# LedTile200mm.net
KiCad netlist of a schematic drawn in EAGLE
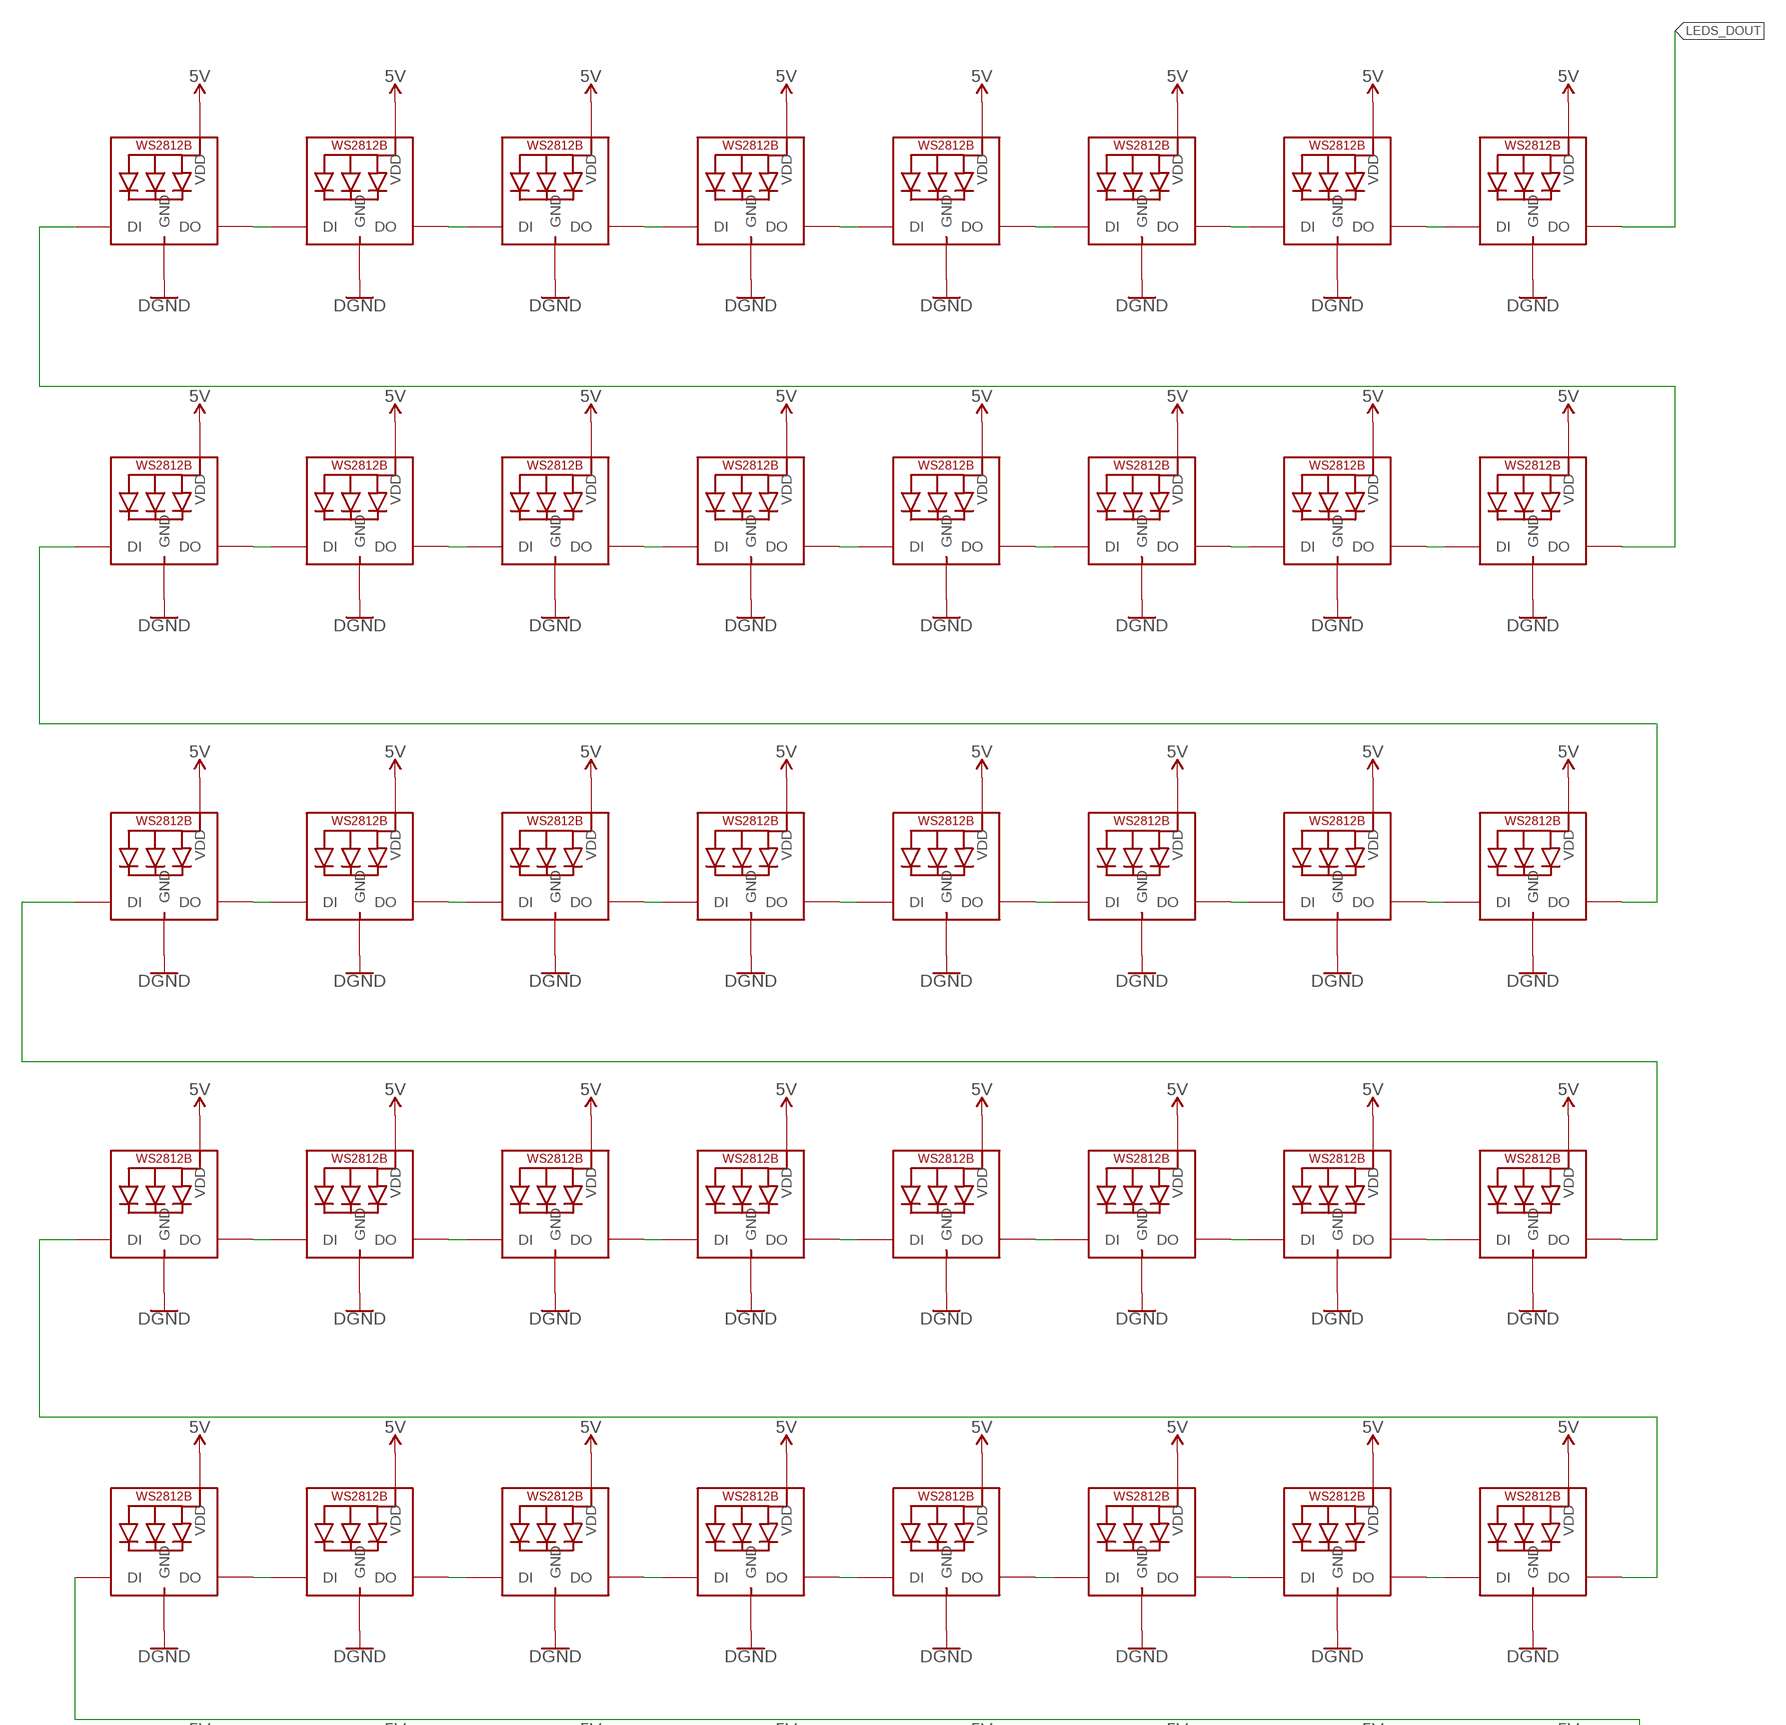
[diagram p0: schematic, sheet 1, part 1 of 3]
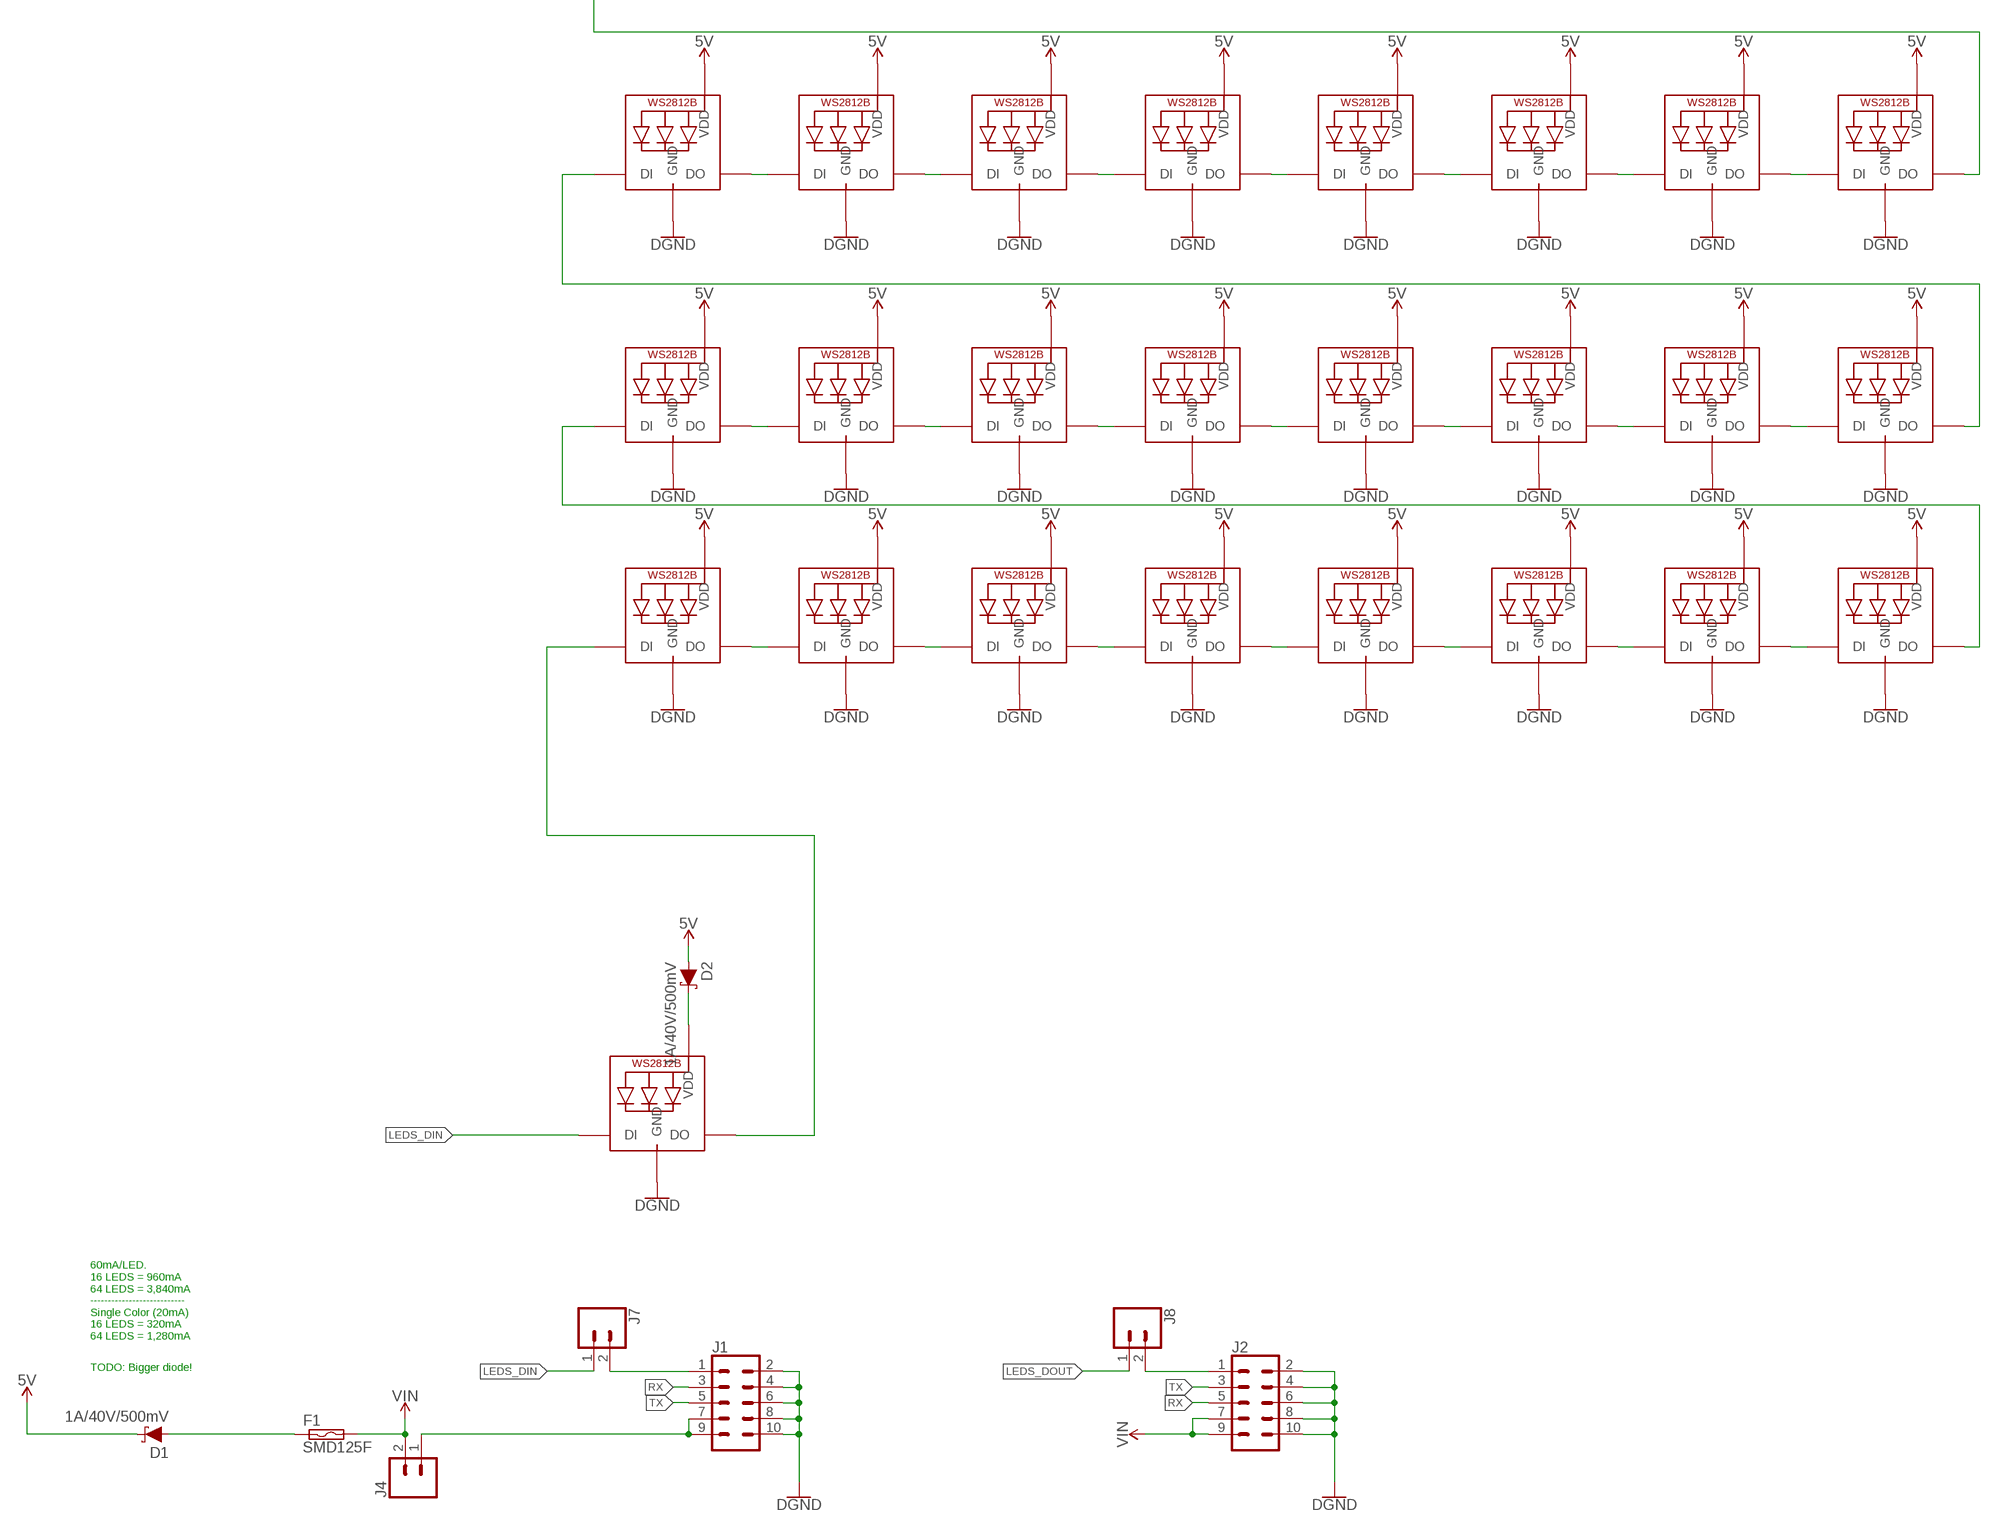
[diagram p1: schematic, sheet 1, part 2 of 3]
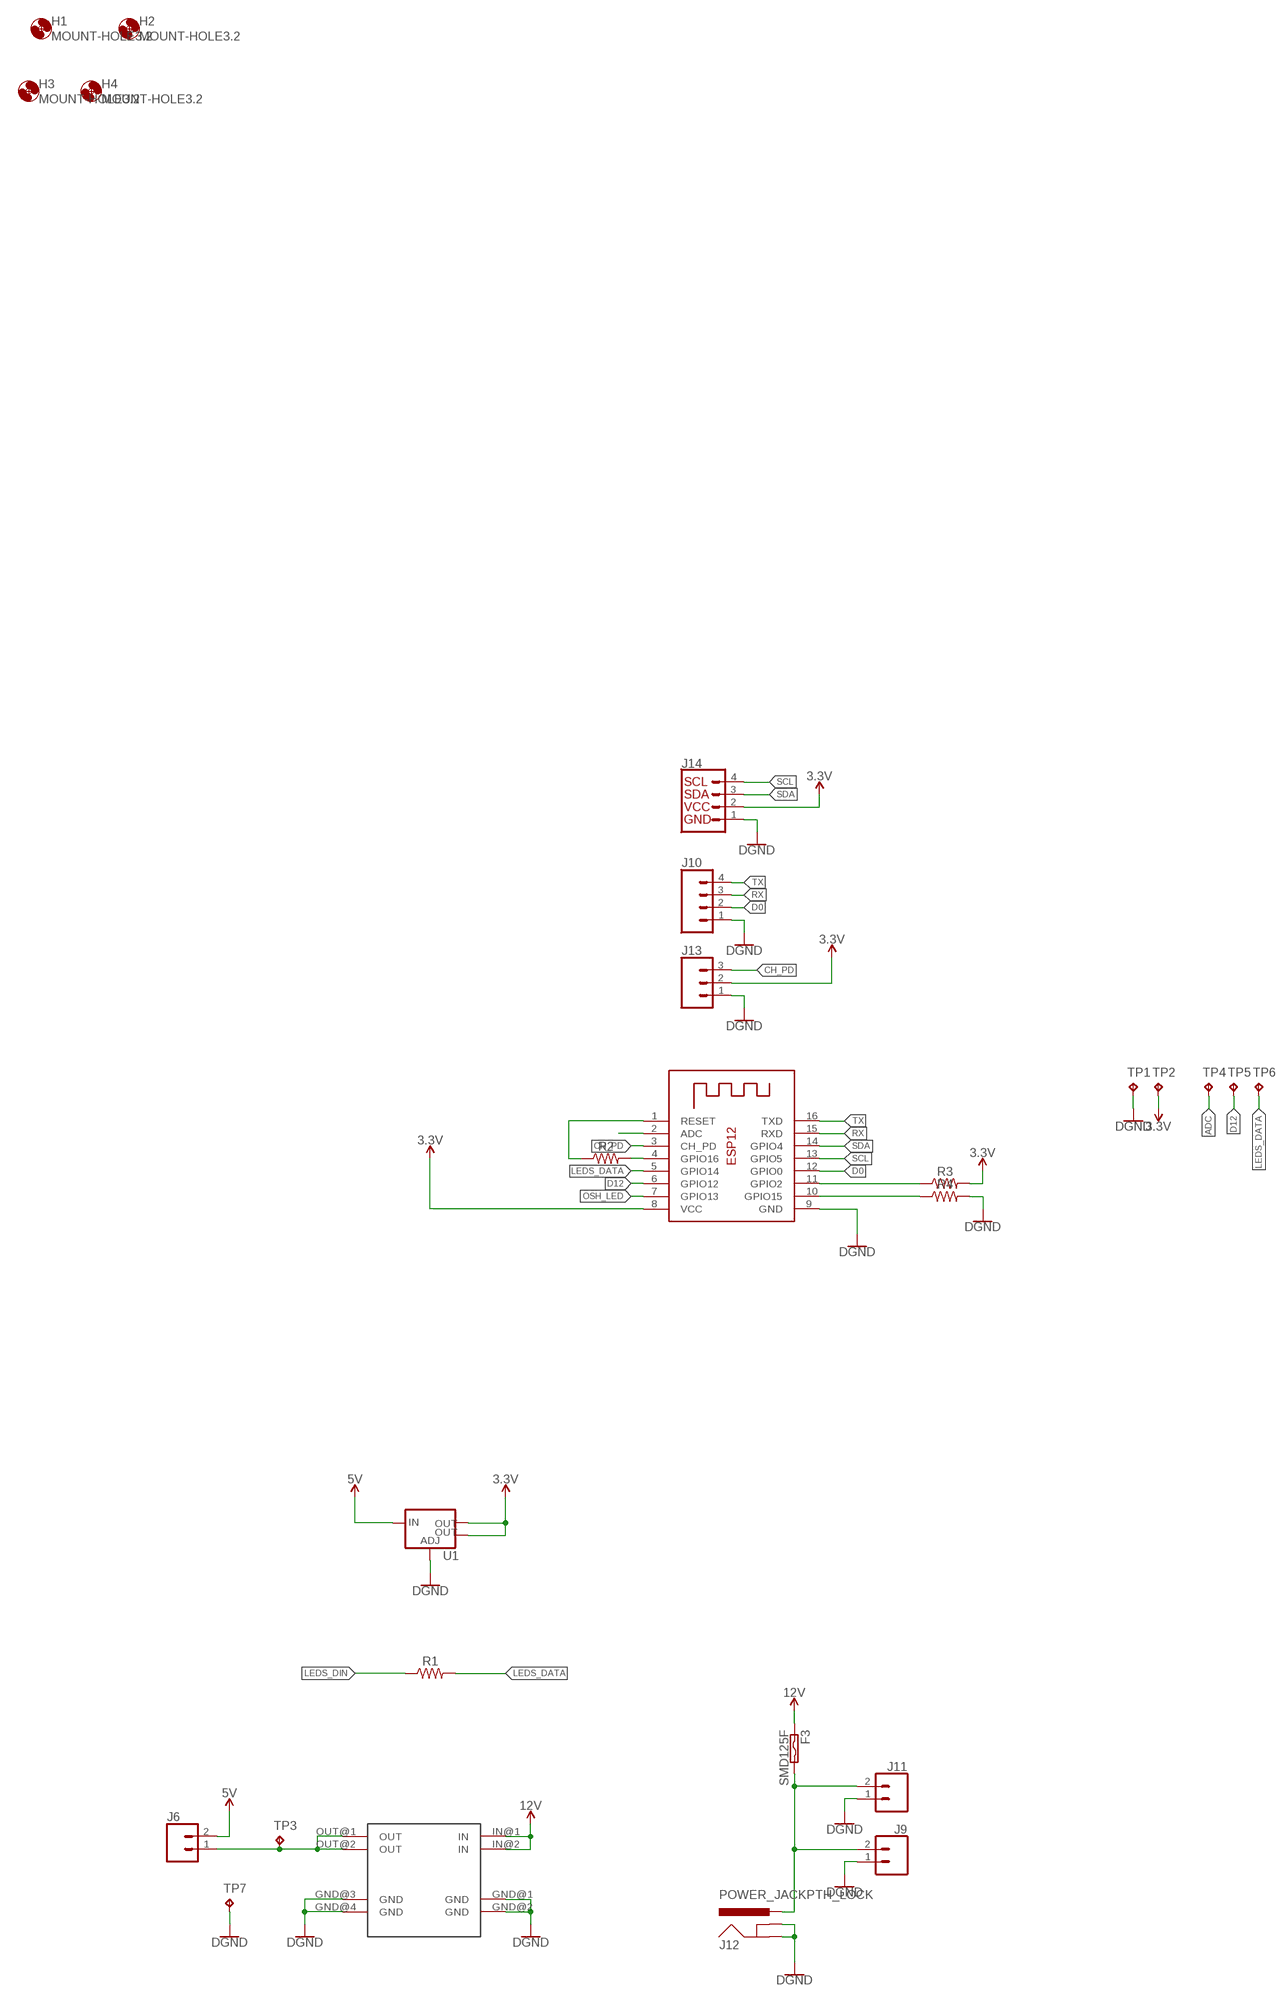
[diagram p2: schematic, sheet 1, part 3 of 3]

(export (version "E")
  (design (tool "Eeschema 10.0.6"))
  (components
    (comp (ref "D1")
      (value "1A/40V/500mV")
      (footprint "eagle-import:SMA-DIODE")
      (libsource (lib "eagle-import") (part "DIODE-SCHOTTKY-SS14"))
    )
    (comp (ref "D2")
      (value "1A/40V/500mV")
      (footprint "eagle-import:SMA-DIODE")
      (libsource (lib "eagle-import") (part "DIODE-SCHOTTKY-SS14"))
    )
    (comp (ref "F1")
      (value "SMD125F")
      (footprint "eagle-import:SMD050F")
      (libsource (lib "eagle-import") (part "SMDF125"))
    )
    (comp (ref "F3")
      (value "SMD125F")
      (footprint "eagle-import:SMD050F")
      (libsource (lib "eagle-import") (part "SMDF125"))
    )
    (comp (ref "H1")
      (value "MOUNT-HOLE3.2")
      (footprint "eagle-import:3,2")
      (libsource (lib "eagle-import") (part "MOUNT-HOLE3.2"))
    )
    (comp (ref "H2")
      (value "MOUNT-HOLE3.2")
      (footprint "eagle-import:3,2")
      (libsource (lib "eagle-import") (part "MOUNT-HOLE3.2"))
    )
    (comp (ref "H3")
      (value "MOUNT-HOLE3.2")
      (footprint "eagle-import:3,2")
      (libsource (lib "eagle-import") (part "MOUNT-HOLE3.2"))
    )
    (comp (ref "H4")
      (value "MOUNT-HOLE3.2")
      (footprint "eagle-import:3,2")
      (libsource (lib "eagle-import") (part "MOUNT-HOLE3.2"))
    )
    (comp (ref "J1")
      (value "CONN_05X2RA")
      (footprint "eagle-import:2X5-RA")
      (libsource (lib "eagle-import") (part "CONN_05X2RA"))
    )
    (comp (ref "J2")
      (value "CONN_05X2RA")
      (footprint "eagle-import:2X5-RA")
      (libsource (lib "eagle-import") (part "CONN_05X2RA"))
    )
    (comp (ref "J4")
      (value "CONN_02")
      (footprint "eagle-import:1X02")
      (libsource (lib "eagle-import") (part "CONN_02"))
    )
    (comp (ref "J6")
      (value "CONN_02")
      (footprint "eagle-import:1X02")
      (libsource (lib "eagle-import") (part "CONN_02"))
    )
    (comp (ref "J7")
      (value "CONN_02")
      (footprint "eagle-import:1X02")
      (libsource (lib "eagle-import") (part "CONN_02"))
    )
    (comp (ref "J8")
      (value "CONN_02")
      (footprint "eagle-import:1X02")
      (libsource (lib "eagle-import") (part "CONN_02"))
    )
    (comp (ref "J9")
      (value "CONN_025MM")
      (footprint "eagle-import:SCREWTERMINAL-5MM-2")
      (libsource (lib "eagle-import") (part "CONN_025MM"))
    )
    (comp (ref "J10")
      (value "CONN_04")
      (footprint "eagle-import:1X04")
      (libsource (lib "eagle-import") (part "CONN_04"))
    )
    (comp (ref "J11")
      (value "CONN_025MM")
      (footprint "eagle-import:SCREWTERMINAL-5MM-2")
      (libsource (lib "eagle-import") (part "CONN_025MM"))
    )
    (comp (ref "J12")
      (value "POWER_JACKPTH_LOCK")
      (footprint "eagle-import:POWER_JACK_PTH_LOCK")
      (libsource (lib "eagle-import") (part "POWER_JACKPTH_LOCK"))
    )
    (comp (ref "J13")
      (value "CONN_03")
      (footprint "eagle-import:1X03")
      (libsource (lib "eagle-import") (part "CONN_03"))
    )
    (comp (ref "J14")
      (value "I2C_STANDARD")
      (footprint "eagle-import:1X04")
      (libsource (lib "eagle-import") (part "I2C_STANDARD"))
    )
    (comp (ref "LED1")
      (value "WS2812B5050")
      (footprint "eagle-import:WS2812B")
      (libsource (lib "eagle-import") (part "WS2812B5050"))
    )
    (comp (ref "LED2")
      (value "WS2812B5050")
      (footprint "eagle-import:WS2812B")
      (libsource (lib "eagle-import") (part "WS2812B5050"))
    )
    (comp (ref "LED3")
      (value "WS2812B5050")
      (footprint "eagle-import:WS2812B")
      (libsource (lib "eagle-import") (part "WS2812B5050"))
    )
    (comp (ref "LED4")
      (value "WS2812B5050")
      (footprint "eagle-import:WS2812B")
      (libsource (lib "eagle-import") (part "WS2812B5050"))
    )
    (comp (ref "LED5")
      (value "WS2812B5050")
      (footprint "eagle-import:WS2812B")
      (libsource (lib "eagle-import") (part "WS2812B5050"))
    )
    (comp (ref "LED6")
      (value "WS2812B5050")
      (footprint "eagle-import:WS2812B")
      (libsource (lib "eagle-import") (part "WS2812B5050"))
    )
    (comp (ref "LED7")
      (value "WS2812B5050")
      (footprint "eagle-import:WS2812B")
      (libsource (lib "eagle-import") (part "WS2812B5050"))
    )
    (comp (ref "LED8")
      (value "WS2812B5050")
      (footprint "eagle-import:WS2812B")
      (libsource (lib "eagle-import") (part "WS2812B5050"))
    )
    (comp (ref "LED9")
      (value "WS2812B5050")
      (footprint "eagle-import:WS2812B")
      (libsource (lib "eagle-import") (part "WS2812B5050"))
    )
    (comp (ref "LED10")
      (value "WS2812B5050")
      (footprint "eagle-import:WS2812B")
      (libsource (lib "eagle-import") (part "WS2812B5050"))
    )
    (comp (ref "LED11")
      (value "WS2812B5050")
      (footprint "eagle-import:WS2812B")
      (libsource (lib "eagle-import") (part "WS2812B5050"))
    )
    (comp (ref "LED12")
      (value "WS2812B5050")
      (footprint "eagle-import:WS2812B")
      (libsource (lib "eagle-import") (part "WS2812B5050"))
    )
    (comp (ref "LED13")
      (value "WS2812B5050")
      (footprint "eagle-import:WS2812B")
      (libsource (lib "eagle-import") (part "WS2812B5050"))
    )
    (comp (ref "LED14")
      (value "WS2812B5050")
      (footprint "eagle-import:WS2812B")
      (libsource (lib "eagle-import") (part "WS2812B5050"))
    )
    (comp (ref "LED15")
      (value "WS2812B5050")
      (footprint "eagle-import:WS2812B")
      (libsource (lib "eagle-import") (part "WS2812B5050"))
    )
    (comp (ref "LED16")
      (value "WS2812B5050")
      (footprint "eagle-import:WS2812B")
      (libsource (lib "eagle-import") (part "WS2812B5050"))
    )
    (comp (ref "LED17")
      (value "WS2812B5050")
      (footprint "eagle-import:WS2812B")
      (libsource (lib "eagle-import") (part "WS2812B5050"))
    )
    (comp (ref "LED18")
      (value "WS2812B5050")
      (footprint "eagle-import:WS2812B")
      (libsource (lib "eagle-import") (part "WS2812B5050"))
    )
    (comp (ref "LED19")
      (value "WS2812B5050")
      (footprint "eagle-import:WS2812B")
      (libsource (lib "eagle-import") (part "WS2812B5050"))
    )
    (comp (ref "LED20")
      (value "WS2812B5050")
      (footprint "eagle-import:WS2812B")
      (libsource (lib "eagle-import") (part "WS2812B5050"))
    )
    (comp (ref "LED21")
      (value "WS2812B5050")
      (footprint "eagle-import:WS2812B")
      (libsource (lib "eagle-import") (part "WS2812B5050"))
    )
    (comp (ref "LED22")
      (value "WS2812B5050")
      (footprint "eagle-import:WS2812B")
      (libsource (lib "eagle-import") (part "WS2812B5050"))
    )
    (comp (ref "LED23")
      (value "WS2812B5050")
      (footprint "eagle-import:WS2812B")
      (libsource (lib "eagle-import") (part "WS2812B5050"))
    )
    (comp (ref "LED24")
      (value "WS2812B5050")
      (footprint "eagle-import:WS2812B")
      (libsource (lib "eagle-import") (part "WS2812B5050"))
    )
    (comp (ref "LED25")
      (value "WS2812B5050")
      (footprint "eagle-import:WS2812B")
      (libsource (lib "eagle-import") (part "WS2812B5050"))
    )
    (comp (ref "LED26")
      (value "WS2812B5050")
      (footprint "eagle-import:WS2812B")
      (libsource (lib "eagle-import") (part "WS2812B5050"))
    )
    (comp (ref "LED27")
      (value "WS2812B5050")
      (footprint "eagle-import:WS2812B")
      (libsource (lib "eagle-import") (part "WS2812B5050"))
    )
    (comp (ref "LED28")
      (value "WS2812B5050")
      (footprint "eagle-import:WS2812B")
      (libsource (lib "eagle-import") (part "WS2812B5050"))
    )
    (comp (ref "LED29")
      (value "WS2812B5050")
      (footprint "eagle-import:WS2812B")
      (libsource (lib "eagle-import") (part "WS2812B5050"))
    )
    (comp (ref "LED30")
      (value "WS2812B5050")
      (footprint "eagle-import:WS2812B")
      (libsource (lib "eagle-import") (part "WS2812B5050"))
    )
    (comp (ref "LED31")
      (value "WS2812B5050")
      (footprint "eagle-import:WS2812B")
      (libsource (lib "eagle-import") (part "WS2812B5050"))
    )
    (comp (ref "LED32")
      (value "WS2812B5050")
      (footprint "eagle-import:WS2812B")
      (libsource (lib "eagle-import") (part "WS2812B5050"))
    )
    (comp (ref "LED33")
      (value "WS2812B5050")
      (footprint "eagle-import:WS2812B")
      (libsource (lib "eagle-import") (part "WS2812B5050"))
    )
    (comp (ref "LED34")
      (value "WS2812B5050")
      (footprint "eagle-import:WS2812B")
      (libsource (lib "eagle-import") (part "WS2812B5050"))
    )
    (comp (ref "LED35")
      (value "WS2812B5050")
      (footprint "eagle-import:WS2812B")
      (libsource (lib "eagle-import") (part "WS2812B5050"))
    )
    (comp (ref "LED36")
      (value "WS2812B5050")
      (footprint "eagle-import:WS2812B")
      (libsource (lib "eagle-import") (part "WS2812B5050"))
    )
    (comp (ref "LED37")
      (value "WS2812B5050")
      (footprint "eagle-import:WS2812B")
      (libsource (lib "eagle-import") (part "WS2812B5050"))
    )
    (comp (ref "LED38")
      (value "WS2812B5050")
      (footprint "eagle-import:WS2812B")
      (libsource (lib "eagle-import") (part "WS2812B5050"))
    )
    (comp (ref "LED39")
      (value "WS2812B5050")
      (footprint "eagle-import:WS2812B")
      (libsource (lib "eagle-import") (part "WS2812B5050"))
    )
    (comp (ref "LED40")
      (value "WS2812B5050")
      (footprint "eagle-import:WS2812B")
      (libsource (lib "eagle-import") (part "WS2812B5050"))
    )
    (comp (ref "LED41")
      (value "WS2812B5050")
      (footprint "eagle-import:WS2812B")
      (libsource (lib "eagle-import") (part "WS2812B5050"))
    )
    (comp (ref "LED42")
      (value "WS2812B5050")
      (footprint "eagle-import:WS2812B")
      (libsource (lib "eagle-import") (part "WS2812B5050"))
    )
    (comp (ref "LED43")
      (value "WS2812B5050")
      (footprint "eagle-import:WS2812B")
      (libsource (lib "eagle-import") (part "WS2812B5050"))
    )
    (comp (ref "LED44")
      (value "WS2812B5050")
      (footprint "eagle-import:WS2812B")
      (libsource (lib "eagle-import") (part "WS2812B5050"))
    )
    (comp (ref "LED45")
      (value "WS2812B5050")
      (footprint "eagle-import:WS2812B")
      (libsource (lib "eagle-import") (part "WS2812B5050"))
    )
    (comp (ref "LED46")
      (value "WS2812B5050")
      (footprint "eagle-import:WS2812B")
      (libsource (lib "eagle-import") (part "WS2812B5050"))
    )
    (comp (ref "LED47")
      (value "WS2812B5050")
      (footprint "eagle-import:WS2812B")
      (libsource (lib "eagle-import") (part "WS2812B5050"))
    )
    (comp (ref "LED48")
      (value "WS2812B5050")
      (footprint "eagle-import:WS2812B")
      (libsource (lib "eagle-import") (part "WS2812B5050"))
    )
    (comp (ref "LED49")
      (value "WS2812B5050")
      (footprint "eagle-import:WS2812B")
      (libsource (lib "eagle-import") (part "WS2812B5050"))
    )
    (comp (ref "LED50")
      (value "WS2812B5050")
      (footprint "eagle-import:WS2812B")
      (libsource (lib "eagle-import") (part "WS2812B5050"))
    )
    (comp (ref "LED51")
      (value "WS2812B5050")
      (footprint "eagle-import:WS2812B")
      (libsource (lib "eagle-import") (part "WS2812B5050"))
    )
    (comp (ref "LED52")
      (value "WS2812B5050")
      (footprint "eagle-import:WS2812B")
      (libsource (lib "eagle-import") (part "WS2812B5050"))
    )
    (comp (ref "LED53")
      (value "WS2812B5050")
      (footprint "eagle-import:WS2812B")
      (libsource (lib "eagle-import") (part "WS2812B5050"))
    )
    (comp (ref "LED54")
      (value "WS2812B5050")
      (footprint "eagle-import:WS2812B")
      (libsource (lib "eagle-import") (part "WS2812B5050"))
    )
    (comp (ref "LED55")
      (value "WS2812B5050")
      (footprint "eagle-import:WS2812B")
      (libsource (lib "eagle-import") (part "WS2812B5050"))
    )
    (comp (ref "LED56")
      (value "WS2812B5050")
      (footprint "eagle-import:WS2812B")
      (libsource (lib "eagle-import") (part "WS2812B5050"))
    )
    (comp (ref "LED57")
      (value "WS2812B5050")
      (footprint "eagle-import:WS2812B")
      (libsource (lib "eagle-import") (part "WS2812B5050"))
    )
    (comp (ref "LED58")
      (value "WS2812B5050")
      (footprint "eagle-import:WS2812B")
      (libsource (lib "eagle-import") (part "WS2812B5050"))
    )
    (comp (ref "LED59")
      (value "WS2812B5050")
      (footprint "eagle-import:WS2812B")
      (libsource (lib "eagle-import") (part "WS2812B5050"))
    )
    (comp (ref "LED60")
      (value "WS2812B5050")
      (footprint "eagle-import:WS2812B")
      (libsource (lib "eagle-import") (part "WS2812B5050"))
    )
    (comp (ref "LED61")
      (value "WS2812B5050")
      (footprint "eagle-import:WS2812B")
      (libsource (lib "eagle-import") (part "WS2812B5050"))
    )
    (comp (ref "LED62")
      (value "WS2812B5050")
      (footprint "eagle-import:WS2812B")
      (libsource (lib "eagle-import") (part "WS2812B5050"))
    )
    (comp (ref "LED63")
      (value "WS2812B5050")
      (footprint "eagle-import:WS2812B")
      (libsource (lib "eagle-import") (part "WS2812B5050"))
    )
    (comp (ref "LED64")
      (value "WS2812B5050")
      (footprint "eagle-import:WS2812B")
      (libsource (lib "eagle-import") (part "WS2812B5050"))
    )
    (comp (ref "LED65")
      (value "WS2812B5050")
      (footprint "eagle-import:WS2812B")
      (libsource (lib "eagle-import") (part "WS2812B5050"))
    )
    (comp (ref "R1")
      (value "RESISTOR0805")
      (footprint "eagle-import:0805")
      (libsource (lib "eagle-import") (part "RESISTOR0805"))
    )
    (comp (ref "R2")
      (value "RESISTOR0805")
      (footprint "eagle-import:0805")
      (libsource (lib "eagle-import") (part "RESISTOR0805"))
    )
    (comp (ref "R3")
      (value "RESISTOR0805")
      (footprint "eagle-import:0805")
      (libsource (lib "eagle-import") (part "RESISTOR0805"))
    )
    (comp (ref "R4")
      (value "RESISTOR0805")
      (footprint "eagle-import:0805")
      (libsource (lib "eagle-import") (part "RESISTOR0805"))
    )
    (comp (ref "TP1")
      (value "TPTP16R")
      (footprint "eagle-import:TP16R")
      (libsource (lib "eagle-import") (part "TPTP16R"))
    )
    (comp (ref "TP2")
      (value "TPTP16R")
      (footprint "eagle-import:TP16R")
      (libsource (lib "eagle-import") (part "TPTP16R"))
    )
    (comp (ref "TP3")
      (value "TPTP16R")
      (footprint "eagle-import:TP16R")
      (libsource (lib "eagle-import") (part "TPTP16R"))
    )
    (comp (ref "TP4")
      (value "TPTP16R")
      (footprint "eagle-import:TP16R")
      (libsource (lib "eagle-import") (part "TPTP16R"))
    )
    (comp (ref "TP5")
      (value "TPTP16R")
      (footprint "eagle-import:TP16R")
      (libsource (lib "eagle-import") (part "TPTP16R"))
    )
    (comp (ref "TP6")
      (value "TPTP16R")
      (footprint "eagle-import:TP16R")
      (libsource (lib "eagle-import") (part "TPTP16R"))
    )
    (comp (ref "TP7")
      (value "TPTP16R")
      (footprint "eagle-import:TP16R")
      (libsource (lib "eagle-import") (part "TPTP16R"))
    )
    (comp (ref "U$1")
      (value "MINI-BUCK-MODULE-3A")
      (footprint "eagle-import:MINI-BUCK-MODULE-3A")
      (libsource (lib "eagle-import") (part "MINI-BUCK-MODULE-3A"))
    )
    (comp (ref "U1")
      (value "V_REG_LM1117SOT223")
      (footprint "eagle-import:SOT223")
      (libsource (lib "eagle-import") (part "V_REG_LM1117SOT223"))
    )
    (comp (ref "X1")
      (value "ESP-12")
      (footprint "eagle-import:ESP-12")
      (libsource (lib "eagle-import") (part "ESP-12"))
    )
  )
  (nets
    (net (code "1") (name "3.3V") (class "Default")
      (node (ref "J13") (pin "2") (pinfunction "2_2") (pintype "passive"))
      (node (ref "J14") (pin "2") (pinfunction "2_2") (pintype "power_in"))
      (node (ref "R3") (pin "2") (pinfunction "2_2") (pintype "passive"))
      (node (ref "TP2") (pin "TP") (pinfunction "TP_TP") (pintype "input"))
      (node (ref "U1") (pin "2") (pinfunction "OUT_2") (pintype "output"))
      (node (ref "U1") (pin "4") (pinfunction "OUT_4") (pintype "output"))
      (node (ref "X1") (pin "8") (pinfunction "VCC_8") (pintype "power_in"))
    )
    (net (code "2") (name "5V") (class "Default")
      (node (ref "D1") (pin "C") (pinfunction "C_C") (pintype "passive"))
      (node (ref "D2") (pin "A") (pinfunction "A_A") (pintype "passive"))
      (node (ref "J6") (pin "2") (pinfunction "2_2") (pintype "passive"))
      (node (ref "LED1") (pin "1-VDD") (pinfunction "VDD_1-VDD") (pintype "power_in"))
      (node (ref "LED10") (pin "1-VDD") (pinfunction "VDD_1-VDD") (pintype "power_in"))
      (node (ref "LED11") (pin "1-VDD") (pinfunction "VDD_1-VDD") (pintype "power_in"))
      (node (ref "LED12") (pin "1-VDD") (pinfunction "VDD_1-VDD") (pintype "power_in"))
      (node (ref "LED13") (pin "1-VDD") (pinfunction "VDD_1-VDD") (pintype "power_in"))
      (node (ref "LED14") (pin "1-VDD") (pinfunction "VDD_1-VDD") (pintype "power_in"))
      (node (ref "LED15") (pin "1-VDD") (pinfunction "VDD_1-VDD") (pintype "power_in"))
      (node (ref "LED16") (pin "1-VDD") (pinfunction "VDD_1-VDD") (pintype "power_in"))
      (node (ref "LED17") (pin "1-VDD") (pinfunction "VDD_1-VDD") (pintype "power_in"))
      (node (ref "LED18") (pin "1-VDD") (pinfunction "VDD_1-VDD") (pintype "power_in"))
      (node (ref "LED19") (pin "1-VDD") (pinfunction "VDD_1-VDD") (pintype "power_in"))
      (node (ref "LED2") (pin "1-VDD") (pinfunction "VDD_1-VDD") (pintype "power_in"))
      (node (ref "LED20") (pin "1-VDD") (pinfunction "VDD_1-VDD") (pintype "power_in"))
      (node (ref "LED21") (pin "1-VDD") (pinfunction "VDD_1-VDD") (pintype "power_in"))
      (node (ref "LED22") (pin "1-VDD") (pinfunction "VDD_1-VDD") (pintype "power_in"))
      (node (ref "LED23") (pin "1-VDD") (pinfunction "VDD_1-VDD") (pintype "power_in"))
      (node (ref "LED24") (pin "1-VDD") (pinfunction "VDD_1-VDD") (pintype "power_in"))
      (node (ref "LED25") (pin "1-VDD") (pinfunction "VDD_1-VDD") (pintype "power_in"))
      (node (ref "LED26") (pin "1-VDD") (pinfunction "VDD_1-VDD") (pintype "power_in"))
      (node (ref "LED27") (pin "1-VDD") (pinfunction "VDD_1-VDD") (pintype "power_in"))
      (node (ref "LED28") (pin "1-VDD") (pinfunction "VDD_1-VDD") (pintype "power_in"))
      (node (ref "LED29") (pin "1-VDD") (pinfunction "VDD_1-VDD") (pintype "power_in"))
      (node (ref "LED3") (pin "1-VDD") (pinfunction "VDD_1-VDD") (pintype "power_in"))
      (node (ref "LED30") (pin "1-VDD") (pinfunction "VDD_1-VDD") (pintype "power_in"))
      (node (ref "LED31") (pin "1-VDD") (pinfunction "VDD_1-VDD") (pintype "power_in"))
      (node (ref "LED32") (pin "1-VDD") (pinfunction "VDD_1-VDD") (pintype "power_in"))
      (node (ref "LED33") (pin "1-VDD") (pinfunction "VDD_1-VDD") (pintype "power_in"))
      (node (ref "LED34") (pin "1-VDD") (pinfunction "VDD_1-VDD") (pintype "power_in"))
      (node (ref "LED35") (pin "1-VDD") (pinfunction "VDD_1-VDD") (pintype "power_in"))
      (node (ref "LED36") (pin "1-VDD") (pinfunction "VDD_1-VDD") (pintype "power_in"))
      (node (ref "LED37") (pin "1-VDD") (pinfunction "VDD_1-VDD") (pintype "power_in"))
      (node (ref "LED38") (pin "1-VDD") (pinfunction "VDD_1-VDD") (pintype "power_in"))
      (node (ref "LED39") (pin "1-VDD") (pinfunction "VDD_1-VDD") (pintype "power_in"))
      (node (ref "LED4") (pin "1-VDD") (pinfunction "VDD_1-VDD") (pintype "power_in"))
      (node (ref "LED40") (pin "1-VDD") (pinfunction "VDD_1-VDD") (pintype "power_in"))
      (node (ref "LED41") (pin "1-VDD") (pinfunction "VDD_1-VDD") (pintype "power_in"))
      (node (ref "LED42") (pin "1-VDD") (pinfunction "VDD_1-VDD") (pintype "power_in"))
      (node (ref "LED43") (pin "1-VDD") (pinfunction "VDD_1-VDD") (pintype "power_in"))
      (node (ref "LED44") (pin "1-VDD") (pinfunction "VDD_1-VDD") (pintype "power_in"))
      (node (ref "LED45") (pin "1-VDD") (pinfunction "VDD_1-VDD") (pintype "power_in"))
      (node (ref "LED46") (pin "1-VDD") (pinfunction "VDD_1-VDD") (pintype "power_in"))
      (node (ref "LED47") (pin "1-VDD") (pinfunction "VDD_1-VDD") (pintype "power_in"))
      (node (ref "LED48") (pin "1-VDD") (pinfunction "VDD_1-VDD") (pintype "power_in"))
      (node (ref "LED49") (pin "1-VDD") (pinfunction "VDD_1-VDD") (pintype "power_in"))
      (node (ref "LED5") (pin "1-VDD") (pinfunction "VDD_1-VDD") (pintype "power_in"))
      (node (ref "LED50") (pin "1-VDD") (pinfunction "VDD_1-VDD") (pintype "power_in"))
      (node (ref "LED51") (pin "1-VDD") (pinfunction "VDD_1-VDD") (pintype "power_in"))
      (node (ref "LED52") (pin "1-VDD") (pinfunction "VDD_1-VDD") (pintype "power_in"))
      (node (ref "LED53") (pin "1-VDD") (pinfunction "VDD_1-VDD") (pintype "power_in"))
      (node (ref "LED54") (pin "1-VDD") (pinfunction "VDD_1-VDD") (pintype "power_in"))
      (node (ref "LED55") (pin "1-VDD") (pinfunction "VDD_1-VDD") (pintype "power_in"))
      (node (ref "LED56") (pin "1-VDD") (pinfunction "VDD_1-VDD") (pintype "power_in"))
      (node (ref "LED57") (pin "1-VDD") (pinfunction "VDD_1-VDD") (pintype "power_in"))
      (node (ref "LED58") (pin "1-VDD") (pinfunction "VDD_1-VDD") (pintype "power_in"))
      (node (ref "LED59") (pin "1-VDD") (pinfunction "VDD_1-VDD") (pintype "power_in"))
      (node (ref "LED6") (pin "1-VDD") (pinfunction "VDD_1-VDD") (pintype "power_in"))
      (node (ref "LED60") (pin "1-VDD") (pinfunction "VDD_1-VDD") (pintype "power_in"))
      (node (ref "LED61") (pin "1-VDD") (pinfunction "VDD_1-VDD") (pintype "power_in"))
      (node (ref "LED62") (pin "1-VDD") (pinfunction "VDD_1-VDD") (pintype "power_in"))
      (node (ref "LED63") (pin "1-VDD") (pinfunction "VDD_1-VDD") (pintype "power_in"))
      (node (ref "LED64") (pin "1-VDD") (pinfunction "VDD_1-VDD") (pintype "power_in"))
      (node (ref "LED7") (pin "1-VDD") (pinfunction "VDD_1-VDD") (pintype "power_in"))
      (node (ref "LED8") (pin "1-VDD") (pinfunction "VDD_1-VDD") (pintype "power_in"))
      (node (ref "LED9") (pin "1-VDD") (pinfunction "VDD_1-VDD") (pintype "power_in"))
      (node (ref "U1") (pin "3") (pinfunction "IN_3") (pintype "input"))
    )
    (net (code "3") (name "12V") (class "Default")
      (node (ref "F3") (pin "1") (pinfunction "1_1") (pintype "passive"))
      (node (ref "U$1") (pin "IN@1") (pinfunction "IN_IN@1") (pintype "bidirectional"))
      (node (ref "U$1") (pin "IN@2") (pinfunction "IN_IN@2") (pintype "bidirectional"))
    )
    (net (code "4") (name "ADC") (class "Default")
      (node (ref "TP4") (pin "TP") (pinfunction "TP_TP") (pintype "input"))
      (node (ref "X1") (pin "2") (pinfunction "ADC_2") (pintype "passive"))
    )
    (net (code "5") (name "CH_PD") (class "Default")
      (node (ref "J13") (pin "3") (pinfunction "3_3") (pintype "passive"))
      (node (ref "X1") (pin "3") (pinfunction "CH_PD_3") (pintype "input"))
    )
    (net (code "6") (name "D0") (class "Default")
      (node (ref "J10") (pin "2") (pinfunction "2_2") (pintype "passive"))
      (node (ref "X1") (pin "12") (pinfunction "GPIO0_12") (pintype "bidirectional"))
    )
    (net (code "7") (name "D12") (class "Default")
      (node (ref "TP5") (pin "TP") (pinfunction "TP_TP") (pintype "input"))
      (node (ref "X1") (pin "6") (pinfunction "GPIO12_6") (pintype "bidirectional"))
    )
    (net (code "8") (name "DGND") (class "Default")
      (node (ref "J1") (pin "10") (pinfunction "10_10") (pintype "passive"))
      (node (ref "J1") (pin "2") (pinfunction "2_2") (pintype "passive"))
      (node (ref "J1") (pin "4") (pinfunction "4_4") (pintype "passive"))
      (node (ref "J1") (pin "6") (pinfunction "6_6") (pintype "passive"))
      (node (ref "J1") (pin "8") (pinfunction "8_8") (pintype "passive"))
      (node (ref "J10") (pin "1") (pinfunction "1_1") (pintype "passive"))
      (node (ref "J11") (pin "1") (pinfunction "1_1") (pintype "passive"))
      (node (ref "J12") (pin "GND") (pinfunction "GND_GND") (pintype "bidirectional"))
      (node (ref "J12") (pin "GNDBREAK") (pinfunction "GNDBREAK_GNDBREAK") (pintype "bidirectional"))
      (node (ref "J13") (pin "1") (pinfunction "1_1") (pintype "passive"))
      (node (ref "J14") (pin "1") (pinfunction "1_1") (pintype "power_in"))
      (node (ref "J2") (pin "10") (pinfunction "10_10") (pintype "passive"))
      (node (ref "J2") (pin "2") (pinfunction "2_2") (pintype "passive"))
      (node (ref "J2") (pin "4") (pinfunction "4_4") (pintype "passive"))
      (node (ref "J2") (pin "6") (pinfunction "6_6") (pintype "passive"))
      (node (ref "J2") (pin "8") (pinfunction "8_8") (pintype "passive"))
      (node (ref "J9") (pin "1") (pinfunction "1_1") (pintype "passive"))
      (node (ref "LED1") (pin "3-GND") (pinfunction "GND_3-GND") (pintype "power_in"))
      (node (ref "LED10") (pin "3-GND") (pinfunction "GND_3-GND") (pintype "power_in"))
      (node (ref "LED11") (pin "3-GND") (pinfunction "GND_3-GND") (pintype "power_in"))
      (node (ref "LED12") (pin "3-GND") (pinfunction "GND_3-GND") (pintype "power_in"))
      (node (ref "LED13") (pin "3-GND") (pinfunction "GND_3-GND") (pintype "power_in"))
      (node (ref "LED14") (pin "3-GND") (pinfunction "GND_3-GND") (pintype "power_in"))
      (node (ref "LED15") (pin "3-GND") (pinfunction "GND_3-GND") (pintype "power_in"))
      (node (ref "LED16") (pin "3-GND") (pinfunction "GND_3-GND") (pintype "power_in"))
      (node (ref "LED17") (pin "3-GND") (pinfunction "GND_3-GND") (pintype "power_in"))
      (node (ref "LED18") (pin "3-GND") (pinfunction "GND_3-GND") (pintype "power_in"))
      (node (ref "LED19") (pin "3-GND") (pinfunction "GND_3-GND") (pintype "power_in"))
      (node (ref "LED2") (pin "3-GND") (pinfunction "GND_3-GND") (pintype "power_in"))
      (node (ref "LED20") (pin "3-GND") (pinfunction "GND_3-GND") (pintype "power_in"))
      (node (ref "LED21") (pin "3-GND") (pinfunction "GND_3-GND") (pintype "power_in"))
      (node (ref "LED22") (pin "3-GND") (pinfunction "GND_3-GND") (pintype "power_in"))
      (node (ref "LED23") (pin "3-GND") (pinfunction "GND_3-GND") (pintype "power_in"))
      (node (ref "LED24") (pin "3-GND") (pinfunction "GND_3-GND") (pintype "power_in"))
      (node (ref "LED25") (pin "3-GND") (pinfunction "GND_3-GND") (pintype "power_in"))
      (node (ref "LED26") (pin "3-GND") (pinfunction "GND_3-GND") (pintype "power_in"))
      (node (ref "LED27") (pin "3-GND") (pinfunction "GND_3-GND") (pintype "power_in"))
      (node (ref "LED28") (pin "3-GND") (pinfunction "GND_3-GND") (pintype "power_in"))
      (node (ref "LED29") (pin "3-GND") (pinfunction "GND_3-GND") (pintype "power_in"))
      (node (ref "LED3") (pin "3-GND") (pinfunction "GND_3-GND") (pintype "power_in"))
      (node (ref "LED30") (pin "3-GND") (pinfunction "GND_3-GND") (pintype "power_in"))
      (node (ref "LED31") (pin "3-GND") (pinfunction "GND_3-GND") (pintype "power_in"))
      (node (ref "LED32") (pin "3-GND") (pinfunction "GND_3-GND") (pintype "power_in"))
      (node (ref "LED33") (pin "3-GND") (pinfunction "GND_3-GND") (pintype "power_in"))
      (node (ref "LED34") (pin "3-GND") (pinfunction "GND_3-GND") (pintype "power_in"))
      (node (ref "LED35") (pin "3-GND") (pinfunction "GND_3-GND") (pintype "power_in"))
      (node (ref "LED36") (pin "3-GND") (pinfunction "GND_3-GND") (pintype "power_in"))
      (node (ref "LED37") (pin "3-GND") (pinfunction "GND_3-GND") (pintype "power_in"))
      (node (ref "LED38") (pin "3-GND") (pinfunction "GND_3-GND") (pintype "power_in"))
      (node (ref "LED39") (pin "3-GND") (pinfunction "GND_3-GND") (pintype "power_in"))
      (node (ref "LED4") (pin "3-GND") (pinfunction "GND_3-GND") (pintype "power_in"))
      (node (ref "LED40") (pin "3-GND") (pinfunction "GND_3-GND") (pintype "power_in"))
      (node (ref "LED41") (pin "3-GND") (pinfunction "GND_3-GND") (pintype "power_in"))
      (node (ref "LED42") (pin "3-GND") (pinfunction "GND_3-GND") (pintype "power_in"))
      (node (ref "LED43") (pin "3-GND") (pinfunction "GND_3-GND") (pintype "power_in"))
      (node (ref "LED44") (pin "3-GND") (pinfunction "GND_3-GND") (pintype "power_in"))
      (node (ref "LED45") (pin "3-GND") (pinfunction "GND_3-GND") (pintype "power_in"))
      (node (ref "LED46") (pin "3-GND") (pinfunction "GND_3-GND") (pintype "power_in"))
      (node (ref "LED47") (pin "3-GND") (pinfunction "GND_3-GND") (pintype "power_in"))
      (node (ref "LED48") (pin "3-GND") (pinfunction "GND_3-GND") (pintype "power_in"))
      (node (ref "LED49") (pin "3-GND") (pinfunction "GND_3-GND") (pintype "power_in"))
      (node (ref "LED5") (pin "3-GND") (pinfunction "GND_3-GND") (pintype "power_in"))
      (node (ref "LED50") (pin "3-GND") (pinfunction "GND_3-GND") (pintype "power_in"))
      (node (ref "LED51") (pin "3-GND") (pinfunction "GND_3-GND") (pintype "power_in"))
      (node (ref "LED52") (pin "3-GND") (pinfunction "GND_3-GND") (pintype "power_in"))
      (node (ref "LED53") (pin "3-GND") (pinfunction "GND_3-GND") (pintype "power_in"))
      (node (ref "LED54") (pin "3-GND") (pinfunction "GND_3-GND") (pintype "power_in"))
      (node (ref "LED55") (pin "3-GND") (pinfunction "GND_3-GND") (pintype "power_in"))
      (node (ref "LED56") (pin "3-GND") (pinfunction "GND_3-GND") (pintype "power_in"))
      (node (ref "LED57") (pin "3-GND") (pinfunction "GND_3-GND") (pintype "power_in"))
      (node (ref "LED58") (pin "3-GND") (pinfunction "GND_3-GND") (pintype "power_in"))
      (node (ref "LED59") (pin "3-GND") (pinfunction "GND_3-GND") (pintype "power_in"))
      (node (ref "LED6") (pin "3-GND") (pinfunction "GND_3-GND") (pintype "power_in"))
      (node (ref "LED60") (pin "3-GND") (pinfunction "GND_3-GND") (pintype "power_in"))
      (node (ref "LED61") (pin "3-GND") (pinfunction "GND_3-GND") (pintype "power_in"))
      (node (ref "LED62") (pin "3-GND") (pinfunction "GND_3-GND") (pintype "power_in"))
      (node (ref "LED63") (pin "3-GND") (pinfunction "GND_3-GND") (pintype "power_in"))
      (node (ref "LED64") (pin "3-GND") (pinfunction "GND_3-GND") (pintype "power_in"))
      (node (ref "LED65") (pin "3-GND") (pinfunction "GND_3-GND") (pintype "power_in"))
      (node (ref "LED7") (pin "3-GND") (pinfunction "GND_3-GND") (pintype "power_in"))
      (node (ref "LED8") (pin "3-GND") (pinfunction "GND_3-GND") (pintype "power_in"))
      (node (ref "LED9") (pin "3-GND") (pinfunction "GND_3-GND") (pintype "power_in"))
      (node (ref "R4") (pin "2") (pinfunction "2_2") (pintype "passive"))
      (node (ref "TP1") (pin "TP") (pinfunction "TP_TP") (pintype "input"))
      (node (ref "TP7") (pin "TP") (pinfunction "TP_TP") (pintype "input"))
      (node (ref "U$1") (pin "GND@1") (pinfunction "GND_GND@1") (pintype "bidirectional"))
      (node (ref "U$1") (pin "GND@2") (pinfunction "GND_GND@2") (pintype "bidirectional"))
      (node (ref "U$1") (pin "GND@3") (pinfunction "GND_GND@3") (pintype "bidirectional"))
      (node (ref "U$1") (pin "GND@4") (pinfunction "GND_GND@4") (pintype "bidirectional"))
      (node (ref "U1") (pin "1") (pinfunction "ADJ_1") (pintype "input"))
      (node (ref "X1") (pin "9") (pinfunction "GND_9") (pintype "power_in"))
    )
    (net (code "9") (name "LEDS_DATA") (class "Default")
      (node (ref "R1") (pin "2") (pinfunction "2_2") (pintype "passive"))
      (node (ref "TP6") (pin "TP") (pinfunction "TP_TP") (pintype "input"))
      (node (ref "X1") (pin "5") (pinfunction "GPIO14_5") (pintype "bidirectional"))
    )
    (net (code "10") (name "LEDS_DIN") (class "Default")
      (node (ref "J7") (pin "1") (pinfunction "1_1") (pintype "passive"))
      (node (ref "LED65") (pin "4-DIN") (pinfunction "DI_4-DIN") (pintype "input"))
      (node (ref "R1") (pin "1") (pinfunction "1_1") (pintype "passive"))
    )
    (net (code "11") (name "LEDS_DOUT") (class "Default")
      (node (ref "J8") (pin "1") (pinfunction "1_1") (pintype "passive"))
      (node (ref "LED64") (pin "2-DOUT") (pinfunction "DO_2-DOUT") (pintype "output"))
    )
    (net (code "12") (name "Net-(D1-PadA)") (class "Default")
      (node (ref "D1") (pin "A") (pinfunction "A_A") (pintype "passive"))
      (node (ref "F1") (pin "1") (pinfunction "1_1") (pintype "passive"))
    )
    (net (code "13") (name "Net-(F3-Pad2)") (class "Default")
      (node (ref "F3") (pin "2") (pinfunction "2_2") (pintype "passive"))
      (node (ref "J11") (pin "2") (pinfunction "2_2") (pintype "passive"))
      (node (ref "J12") (pin "PWR") (pinfunction "PWR_PWR") (pintype "bidirectional"))
      (node (ref "J9") (pin "2") (pinfunction "2_2") (pintype "passive"))
    )
    (net (code "14") (name "Net-(J1-Pad1)") (class "Default")
      (node (ref "J1") (pin "1") (pinfunction "1_1") (pintype "passive"))
      (node (ref "J7") (pin "2") (pinfunction "2_2") (pintype "passive"))
    )
    (net (code "15") (name "Net-(J1-Pad7)") (class "Default")
      (node (ref "J1") (pin "7") (pinfunction "7_7") (pintype "passive"))
      (node (ref "J1") (pin "9") (pinfunction "9_9") (pintype "passive"))
      (node (ref "J4") (pin "1") (pinfunction "1_1") (pintype "passive"))
    )
    (net (code "16") (name "Net-(J2-Pad1)") (class "Default")
      (node (ref "J2") (pin "1") (pinfunction "1_1") (pintype "passive"))
      (node (ref "J8") (pin "2") (pinfunction "2_2") (pintype "passive"))
    )
    (net (code "17") (name "Net-(J6-Pad1)") (class "Default")
      (node (ref "J6") (pin "1") (pinfunction "1_1") (pintype "passive"))
      (node (ref "TP3") (pin "TP") (pinfunction "TP_TP") (pintype "input"))
      (node (ref "U$1") (pin "OUT@1") (pinfunction "OUT_OUT@1") (pintype "bidirectional"))
      (node (ref "U$1") (pin "OUT@2") (pinfunction "OUT_OUT@2") (pintype "bidirectional"))
    )
    (net (code "18") (name "Net-(LED1-DI)") (class "Default")
      (node (ref "LED1") (pin "4-DIN") (pinfunction "DI_4-DIN") (pintype "input"))
      (node (ref "LED65") (pin "2-DOUT") (pinfunction "DO_2-DOUT") (pintype "output"))
    )
    (net (code "19") (name "Net-(LED1-DO)") (class "Default")
      (node (ref "LED1") (pin "2-DOUT") (pinfunction "DO_2-DOUT") (pintype "output"))
      (node (ref "LED2") (pin "4-DIN") (pinfunction "DI_4-DIN") (pintype "input"))
    )
    (net (code "20") (name "Net-(LED2-DO)") (class "Default")
      (node (ref "LED2") (pin "2-DOUT") (pinfunction "DO_2-DOUT") (pintype "output"))
      (node (ref "LED3") (pin "4-DIN") (pinfunction "DI_4-DIN") (pintype "input"))
    )
    (net (code "21") (name "Net-(LED3-DO)") (class "Default")
      (node (ref "LED3") (pin "2-DOUT") (pinfunction "DO_2-DOUT") (pintype "output"))
      (node (ref "LED4") (pin "4-DIN") (pinfunction "DI_4-DIN") (pintype "input"))
    )
    (net (code "22") (name "Net-(LED4-DO)") (class "Default")
      (node (ref "LED4") (pin "2-DOUT") (pinfunction "DO_2-DOUT") (pintype "output"))
      (node (ref "LED5") (pin "4-DIN") (pinfunction "DI_4-DIN") (pintype "input"))
    )
    (net (code "23") (name "Net-(LED5-DO)") (class "Default")
      (node (ref "LED5") (pin "2-DOUT") (pinfunction "DO_2-DOUT") (pintype "output"))
      (node (ref "LED6") (pin "4-DIN") (pinfunction "DI_4-DIN") (pintype "input"))
    )
    (net (code "24") (name "Net-(LED6-DO)") (class "Default")
      (node (ref "LED6") (pin "2-DOUT") (pinfunction "DO_2-DOUT") (pintype "output"))
      (node (ref "LED7") (pin "4-DIN") (pinfunction "DI_4-DIN") (pintype "input"))
    )
    (net (code "25") (name "Net-(LED7-DO)") (class "Default")
      (node (ref "LED7") (pin "2-DOUT") (pinfunction "DO_2-DOUT") (pintype "output"))
      (node (ref "LED8") (pin "4-DIN") (pinfunction "DI_4-DIN") (pintype "input"))
    )
    (net (code "26") (name "Net-(LED8-DO)") (class "Default")
      (node (ref "LED8") (pin "2-DOUT") (pinfunction "DO_2-DOUT") (pintype "output"))
      (node (ref "LED9") (pin "4-DIN") (pinfunction "DI_4-DIN") (pintype "input"))
    )
    (net (code "27") (name "Net-(LED10-DI)") (class "Default")
      (node (ref "LED10") (pin "4-DIN") (pinfunction "DI_4-DIN") (pintype "input"))
      (node (ref "LED9") (pin "2-DOUT") (pinfunction "DO_2-DOUT") (pintype "output"))
    )
    (net (code "28") (name "Net-(LED10-DO)") (class "Default")
      (node (ref "LED10") (pin "2-DOUT") (pinfunction "DO_2-DOUT") (pintype "output"))
      (node (ref "LED11") (pin "4-DIN") (pinfunction "DI_4-DIN") (pintype "input"))
    )
    (net (code "29") (name "Net-(LED11-DO)") (class "Default")
      (node (ref "LED11") (pin "2-DOUT") (pinfunction "DO_2-DOUT") (pintype "output"))
      (node (ref "LED12") (pin "4-DIN") (pinfunction "DI_4-DIN") (pintype "input"))
    )
    (net (code "30") (name "Net-(LED12-DO)") (class "Default")
      (node (ref "LED12") (pin "2-DOUT") (pinfunction "DO_2-DOUT") (pintype "output"))
      (node (ref "LED13") (pin "4-DIN") (pinfunction "DI_4-DIN") (pintype "input"))
    )
    (net (code "31") (name "Net-(LED13-DO)") (class "Default")
      (node (ref "LED13") (pin "2-DOUT") (pinfunction "DO_2-DOUT") (pintype "output"))
      (node (ref "LED14") (pin "4-DIN") (pinfunction "DI_4-DIN") (pintype "input"))
    )
    (net (code "32") (name "Net-(LED14-DO)") (class "Default")
      (node (ref "LED14") (pin "2-DOUT") (pinfunction "DO_2-DOUT") (pintype "output"))
      (node (ref "LED15") (pin "4-DIN") (pinfunction "DI_4-DIN") (pintype "input"))
    )
    (net (code "33") (name "Net-(LED15-DO)") (class "Default")
      (node (ref "LED15") (pin "2-DOUT") (pinfunction "DO_2-DOUT") (pintype "output"))
      (node (ref "LED16") (pin "4-DIN") (pinfunction "DI_4-DIN") (pintype "input"))
    )
    (net (code "34") (name "Net-(LED16-DO)") (class "Default")
      (node (ref "LED16") (pin "2-DOUT") (pinfunction "DO_2-DOUT") (pintype "output"))
      (node (ref "LED17") (pin "4-DIN") (pinfunction "DI_4-DIN") (pintype "input"))
    )
    (net (code "35") (name "Net-(LED17-DO)") (class "Default")
      (node (ref "LED17") (pin "2-DOUT") (pinfunction "DO_2-DOUT") (pintype "output"))
      (node (ref "LED18") (pin "4-DIN") (pinfunction "DI_4-DIN") (pintype "input"))
    )
    (net (code "36") (name "Net-(LED18-DO)") (class "Default")
      (node (ref "LED18") (pin "2-DOUT") (pinfunction "DO_2-DOUT") (pintype "output"))
      (node (ref "LED19") (pin "4-DIN") (pinfunction "DI_4-DIN") (pintype "input"))
    )
    (net (code "37") (name "Net-(LED19-DO)") (class "Default")
      (node (ref "LED19") (pin "2-DOUT") (pinfunction "DO_2-DOUT") (pintype "output"))
      (node (ref "LED20") (pin "4-DIN") (pinfunction "DI_4-DIN") (pintype "input"))
    )
    (net (code "38") (name "Net-(LED20-DO)") (class "Default")
      (node (ref "LED20") (pin "2-DOUT") (pinfunction "DO_2-DOUT") (pintype "output"))
      (node (ref "LED21") (pin "4-DIN") (pinfunction "DI_4-DIN") (pintype "input"))
    )
    (net (code "39") (name "Net-(LED21-DO)") (class "Default")
      (node (ref "LED21") (pin "2-DOUT") (pinfunction "DO_2-DOUT") (pintype "output"))
      (node (ref "LED22") (pin "4-DIN") (pinfunction "DI_4-DIN") (pintype "input"))
    )
    (net (code "40") (name "Net-(LED22-DO)") (class "Default")
      (node (ref "LED22") (pin "2-DOUT") (pinfunction "DO_2-DOUT") (pintype "output"))
      (node (ref "LED23") (pin "4-DIN") (pinfunction "DI_4-DIN") (pintype "input"))
    )
    (net (code "41") (name "Net-(LED23-DO)") (class "Default")
      (node (ref "LED23") (pin "2-DOUT") (pinfunction "DO_2-DOUT") (pintype "output"))
      (node (ref "LED24") (pin "4-DIN") (pinfunction "DI_4-DIN") (pintype "input"))
    )
    (net (code "42") (name "Net-(LED24-DO)") (class "Default")
      (node (ref "LED24") (pin "2-DOUT") (pinfunction "DO_2-DOUT") (pintype "output"))
      (node (ref "LED25") (pin "4-DIN") (pinfunction "DI_4-DIN") (pintype "input"))
    )
    (net (code "43") (name "Net-(LED25-DO)") (class "Default")
      (node (ref "LED25") (pin "2-DOUT") (pinfunction "DO_2-DOUT") (pintype "output"))
      (node (ref "LED26") (pin "4-DIN") (pinfunction "DI_4-DIN") (pintype "input"))
    )
    (net (code "44") (name "Net-(LED26-DO)") (class "Default")
      (node (ref "LED26") (pin "2-DOUT") (pinfunction "DO_2-DOUT") (pintype "output"))
      (node (ref "LED27") (pin "4-DIN") (pinfunction "DI_4-DIN") (pintype "input"))
    )
    (net (code "45") (name "Net-(LED27-DO)") (class "Default")
      (node (ref "LED27") (pin "2-DOUT") (pinfunction "DO_2-DOUT") (pintype "output"))
      (node (ref "LED28") (pin "4-DIN") (pinfunction "DI_4-DIN") (pintype "input"))
    )
    (net (code "46") (name "Net-(LED28-DO)") (class "Default")
      (node (ref "LED28") (pin "2-DOUT") (pinfunction "DO_2-DOUT") (pintype "output"))
      (node (ref "LED29") (pin "4-DIN") (pinfunction "DI_4-DIN") (pintype "input"))
    )
    (net (code "47") (name "Net-(LED29-DO)") (class "Default")
      (node (ref "LED29") (pin "2-DOUT") (pinfunction "DO_2-DOUT") (pintype "output"))
      (node (ref "LED30") (pin "4-DIN") (pinfunction "DI_4-DIN") (pintype "input"))
    )
    (net (code "48") (name "Net-(LED30-DO)") (class "Default")
      (node (ref "LED30") (pin "2-DOUT") (pinfunction "DO_2-DOUT") (pintype "output"))
      (node (ref "LED31") (pin "4-DIN") (pinfunction "DI_4-DIN") (pintype "input"))
    )
    (net (code "49") (name "Net-(LED31-DO)") (class "Default")
      (node (ref "LED31") (pin "2-DOUT") (pinfunction "DO_2-DOUT") (pintype "output"))
      (node (ref "LED32") (pin "4-DIN") (pinfunction "DI_4-DIN") (pintype "input"))
    )
    (net (code "50") (name "Net-(LED32-DO)") (class "Default")
      (node (ref "LED32") (pin "2-DOUT") (pinfunction "DO_2-DOUT") (pintype "output"))
      (node (ref "LED33") (pin "4-DIN") (pinfunction "DI_4-DIN") (pintype "input"))
    )
    (net (code "51") (name "Net-(LED33-DO)") (class "Default")
      (node (ref "LED33") (pin "2-DOUT") (pinfunction "DO_2-DOUT") (pintype "output"))
      (node (ref "LED34") (pin "4-DIN") (pinfunction "DI_4-DIN") (pintype "input"))
    )
    (net (code "52") (name "Net-(LED34-DO)") (class "Default")
      (node (ref "LED34") (pin "2-DOUT") (pinfunction "DO_2-DOUT") (pintype "output"))
      (node (ref "LED35") (pin "4-DIN") (pinfunction "DI_4-DIN") (pintype "input"))
    )
    (net (code "53") (name "Net-(LED35-DO)") (class "Default")
      (node (ref "LED35") (pin "2-DOUT") (pinfunction "DO_2-DOUT") (pintype "output"))
      (node (ref "LED36") (pin "4-DIN") (pinfunction "DI_4-DIN") (pintype "input"))
    )
    (net (code "54") (name "Net-(LED36-DO)") (class "Default")
      (node (ref "LED36") (pin "2-DOUT") (pinfunction "DO_2-DOUT") (pintype "output"))
      (node (ref "LED37") (pin "4-DIN") (pinfunction "DI_4-DIN") (pintype "input"))
    )
    (net (code "55") (name "Net-(LED37-DO)") (class "Default")
      (node (ref "LED37") (pin "2-DOUT") (pinfunction "DO_2-DOUT") (pintype "output"))
      (node (ref "LED38") (pin "4-DIN") (pinfunction "DI_4-DIN") (pintype "input"))
    )
    (net (code "56") (name "Net-(LED38-DO)") (class "Default")
      (node (ref "LED38") (pin "2-DOUT") (pinfunction "DO_2-DOUT") (pintype "output"))
      (node (ref "LED39") (pin "4-DIN") (pinfunction "DI_4-DIN") (pintype "input"))
    )
    (net (code "57") (name "Net-(LED39-DO)") (class "Default")
      (node (ref "LED39") (pin "2-DOUT") (pinfunction "DO_2-DOUT") (pintype "output"))
      (node (ref "LED40") (pin "4-DIN") (pinfunction "DI_4-DIN") (pintype "input"))
    )
    (net (code "58") (name "Net-(LED40-DO)") (class "Default")
      (node (ref "LED40") (pin "2-DOUT") (pinfunction "DO_2-DOUT") (pintype "output"))
      (node (ref "LED41") (pin "4-DIN") (pinfunction "DI_4-DIN") (pintype "input"))
    )
    (net (code "59") (name "Net-(LED41-DO)") (class "Default")
      (node (ref "LED41") (pin "2-DOUT") (pinfunction "DO_2-DOUT") (pintype "output"))
      (node (ref "LED42") (pin "4-DIN") (pinfunction "DI_4-DIN") (pintype "input"))
    )
    (net (code "60") (name "Net-(LED42-DO)") (class "Default")
      (node (ref "LED42") (pin "2-DOUT") (pinfunction "DO_2-DOUT") (pintype "output"))
      (node (ref "LED43") (pin "4-DIN") (pinfunction "DI_4-DIN") (pintype "input"))
    )
    (net (code "61") (name "Net-(LED43-DO)") (class "Default")
      (node (ref "LED43") (pin "2-DOUT") (pinfunction "DO_2-DOUT") (pintype "output"))
      (node (ref "LED44") (pin "4-DIN") (pinfunction "DI_4-DIN") (pintype "input"))
    )
    (net (code "62") (name "Net-(LED44-DO)") (class "Default")
      (node (ref "LED44") (pin "2-DOUT") (pinfunction "DO_2-DOUT") (pintype "output"))
      (node (ref "LED45") (pin "4-DIN") (pinfunction "DI_4-DIN") (pintype "input"))
    )
    (net (code "63") (name "Net-(LED45-DO)") (class "Default")
      (node (ref "LED45") (pin "2-DOUT") (pinfunction "DO_2-DOUT") (pintype "output"))
      (node (ref "LED46") (pin "4-DIN") (pinfunction "DI_4-DIN") (pintype "input"))
    )
    (net (code "64") (name "Net-(LED46-DO)") (class "Default")
      (node (ref "LED46") (pin "2-DOUT") (pinfunction "DO_2-DOUT") (pintype "output"))
      (node (ref "LED47") (pin "4-DIN") (pinfunction "DI_4-DIN") (pintype "input"))
    )
    (net (code "65") (name "Net-(LED47-DO)") (class "Default")
      (node (ref "LED47") (pin "2-DOUT") (pinfunction "DO_2-DOUT") (pintype "output"))
      (node (ref "LED48") (pin "4-DIN") (pinfunction "DI_4-DIN") (pintype "input"))
    )
    (net (code "66") (name "Net-(LED48-DO)") (class "Default")
      (node (ref "LED48") (pin "2-DOUT") (pinfunction "DO_2-DOUT") (pintype "output"))
      (node (ref "LED49") (pin "4-DIN") (pinfunction "DI_4-DIN") (pintype "input"))
    )
    (net (code "67") (name "Net-(LED49-DO)") (class "Default")
      (node (ref "LED49") (pin "2-DOUT") (pinfunction "DO_2-DOUT") (pintype "output"))
      (node (ref "LED50") (pin "4-DIN") (pinfunction "DI_4-DIN") (pintype "input"))
    )
    (net (code "68") (name "Net-(LED50-DO)") (class "Default")
      (node (ref "LED50") (pin "2-DOUT") (pinfunction "DO_2-DOUT") (pintype "output"))
      (node (ref "LED51") (pin "4-DIN") (pinfunction "DI_4-DIN") (pintype "input"))
    )
    (net (code "69") (name "Net-(LED51-DO)") (class "Default")
      (node (ref "LED51") (pin "2-DOUT") (pinfunction "DO_2-DOUT") (pintype "output"))
      (node (ref "LED52") (pin "4-DIN") (pinfunction "DI_4-DIN") (pintype "input"))
    )
    (net (code "70") (name "Net-(LED52-DO)") (class "Default")
      (node (ref "LED52") (pin "2-DOUT") (pinfunction "DO_2-DOUT") (pintype "output"))
      (node (ref "LED53") (pin "4-DIN") (pinfunction "DI_4-DIN") (pintype "input"))
    )
    (net (code "71") (name "Net-(LED53-DO)") (class "Default")
      (node (ref "LED53") (pin "2-DOUT") (pinfunction "DO_2-DOUT") (pintype "output"))
      (node (ref "LED54") (pin "4-DIN") (pinfunction "DI_4-DIN") (pintype "input"))
    )
    (net (code "72") (name "Net-(LED54-DO)") (class "Default")
      (node (ref "LED54") (pin "2-DOUT") (pinfunction "DO_2-DOUT") (pintype "output"))
      (node (ref "LED55") (pin "4-DIN") (pinfunction "DI_4-DIN") (pintype "input"))
    )
    (net (code "73") (name "Net-(LED55-DO)") (class "Default")
      (node (ref "LED55") (pin "2-DOUT") (pinfunction "DO_2-DOUT") (pintype "output"))
      (node (ref "LED56") (pin "4-DIN") (pinfunction "DI_4-DIN") (pintype "input"))
    )
    (net (code "74") (name "Net-(LED56-DO)") (class "Default")
      (node (ref "LED56") (pin "2-DOUT") (pinfunction "DO_2-DOUT") (pintype "output"))
      (node (ref "LED57") (pin "4-DIN") (pinfunction "DI_4-DIN") (pintype "input"))
    )
    (net (code "75") (name "Net-(LED57-DO)") (class "Default")
      (node (ref "LED57") (pin "2-DOUT") (pinfunction "DO_2-DOUT") (pintype "output"))
      (node (ref "LED58") (pin "4-DIN") (pinfunction "DI_4-DIN") (pintype "input"))
    )
    (net (code "76") (name "Net-(LED58-DO)") (class "Default")
      (node (ref "LED58") (pin "2-DOUT") (pinfunction "DO_2-DOUT") (pintype "output"))
      (node (ref "LED59") (pin "4-DIN") (pinfunction "DI_4-DIN") (pintype "input"))
    )
    (net (code "77") (name "Net-(LED59-DO)") (class "Default")
      (node (ref "LED59") (pin "2-DOUT") (pinfunction "DO_2-DOUT") (pintype "output"))
      (node (ref "LED60") (pin "4-DIN") (pinfunction "DI_4-DIN") (pintype "input"))
    )
    (net (code "78") (name "Net-(LED60-DO)") (class "Default")
      (node (ref "LED60") (pin "2-DOUT") (pinfunction "DO_2-DOUT") (pintype "output"))
      (node (ref "LED61") (pin "4-DIN") (pinfunction "DI_4-DIN") (pintype "input"))
    )
    (net (code "79") (name "Net-(LED61-DO)") (class "Default")
      (node (ref "LED61") (pin "2-DOUT") (pinfunction "DO_2-DOUT") (pintype "output"))
      (node (ref "LED62") (pin "4-DIN") (pinfunction "DI_4-DIN") (pintype "input"))
    )
    (net (code "80") (name "Net-(LED62-DO)") (class "Default")
      (node (ref "LED62") (pin "2-DOUT") (pinfunction "DO_2-DOUT") (pintype "output"))
      (node (ref "LED63") (pin "4-DIN") (pinfunction "DI_4-DIN") (pintype "input"))
    )
    (net (code "81") (name "Net-(LED63-DO)") (class "Default")
      (node (ref "LED63") (pin "2-DOUT") (pinfunction "DO_2-DOUT") (pintype "output"))
      (node (ref "LED64") (pin "4-DIN") (pinfunction "DI_4-DIN") (pintype "input"))
    )
    (net (code "82") (name "Net-(LED65-VDD)") (class "Default")
      (node (ref "D2") (pin "C") (pinfunction "C_C") (pintype "passive"))
      (node (ref "LED65") (pin "1-VDD") (pinfunction "VDD_1-VDD") (pintype "power_in"))
    )
    (net (code "83") (name "Net-(X1-GPIO2)") (class "Default")
      (node (ref "R3") (pin "1") (pinfunction "1_1") (pintype "passive"))
      (node (ref "X1") (pin "11") (pinfunction "GPIO2_11") (pintype "bidirectional"))
    )
    (net (code "84") (name "Net-(X1-GPIO15)") (class "Default")
      (node (ref "R4") (pin "1") (pinfunction "1_1") (pintype "passive"))
      (node (ref "X1") (pin "10") (pinfunction "GPIO15_10") (pintype "bidirectional"))
    )
    (net (code "85") (name "Net-(X1-GPIO16)") (class "Default")
      (node (ref "R2") (pin "2") (pinfunction "2_2") (pintype "passive"))
      (node (ref "X1") (pin "4") (pinfunction "GPIO16_4") (pintype "bidirectional"))
    )
    (net (code "86") (name "Net-(X1-RESET)") (class "Default")
      (node (ref "R2") (pin "1") (pinfunction "1_1") (pintype "passive"))
      (node (ref "X1") (pin "1") (pinfunction "RESET_1") (pintype "input"))
    )
    (net (code "87") (name "OSH_LED") (class "Default")
      (node (ref "X1") (pin "7") (pinfunction "GPIO13_7") (pintype "bidirectional"))
    )
    (net (code "88") (name "RX") (class "Default")
      (node (ref "J1") (pin "3") (pinfunction "3_3") (pintype "passive"))
      (node (ref "J10") (pin "3") (pinfunction "3_3") (pintype "passive"))
      (node (ref "J2") (pin "5") (pinfunction "5_5") (pintype "passive"))
      (node (ref "X1") (pin "15") (pinfunction "RXD_15") (pintype "input"))
    )
    (net (code "89") (name "SCL") (class "Default")
      (node (ref "J14") (pin "4") (pinfunction "4_4") (pintype "passive"))
      (node (ref "X1") (pin "13") (pinfunction "GPIO5_13") (pintype "bidirectional"))
    )
    (net (code "90") (name "SDA") (class "Default")
      (node (ref "J14") (pin "3") (pinfunction "3_3") (pintype "passive"))
      (node (ref "X1") (pin "14") (pinfunction "GPIO4_14") (pintype "bidirectional"))
    )
    (net (code "91") (name "TX") (class "Default")
      (node (ref "J1") (pin "5") (pinfunction "5_5") (pintype "passive"))
      (node (ref "J10") (pin "4") (pinfunction "4_4") (pintype "passive"))
      (node (ref "J2") (pin "3") (pinfunction "3_3") (pintype "passive"))
      (node (ref "X1") (pin "16") (pinfunction "TXD_16") (pintype "output"))
    )
    (net (code "92") (name "VIN") (class "Default")
      (node (ref "F1") (pin "2") (pinfunction "2_2") (pintype "passive"))
      (node (ref "J2") (pin "7") (pinfunction "7_7") (pintype "passive"))
      (node (ref "J2") (pin "9") (pinfunction "9_9") (pintype "passive"))
      (node (ref "J4") (pin "2") (pinfunction "2_2") (pintype "passive"))
    )
  )
)
